# VDMEDA_DisplayMaster.net
KiCad netlist of a schematic drawn in Altium Designer
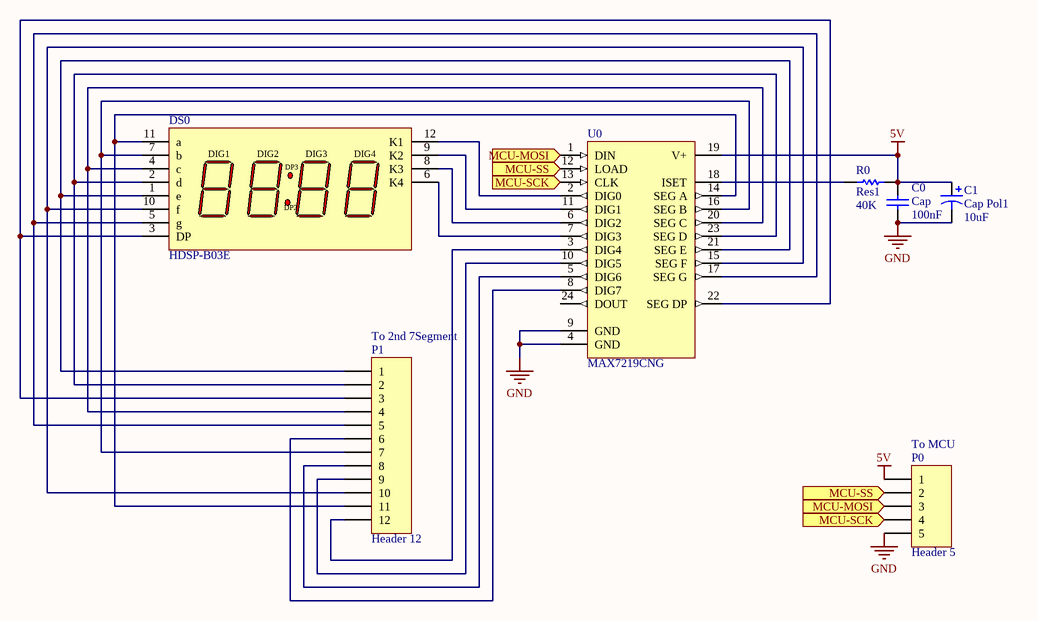
[diagram p0: VDMEDA_DisplayMaster.SchDoc]

(export (version "E")
  (design (tool "Eeschema 10.0.6"))
  (components
    (comp (ref "C0")
      (value "Cap")
      (footprint "RAD-0.3")
      (description "Capacitor")
      (fields (field (name "ALTIUM_VALUE") "100nF") (field (name "PUBLISHER") "Altium Limited"))
      (libsource (lib "Miscellaneous Devices") (part "Cap"))
    )
    (comp (ref "C1")
      (value "Cap Pol1")
      (footprint "RB7.6-15")
      (description "Polarized Capacitor (Radial)")
      (fields (field (name "ALTIUM_VALUE") "10uF") (field (name "PUBLISHER") "Altium Limited"))
      (libsource (lib "Miscellaneous Devices") (part "Cap Pol1"))
    )
    (comp (ref "DS0")
      (value "HDSP-B03E")
      (footprint "B-88")
      (description "14.22 mm GaP HER, Untinted, 88:88 4-Digit 7-Segment Display: CC, Gray Surface")
      (fields (field (name "PUBLISHER") "Altium Limited"))
      (libsource (lib "Agilent LED Display 7-Segment, 4-Digit") (part "HDSP-B03E"))
    )
    (comp (ref "P0")
      (value "Header 5")
      (footprint "HDR1X5")
      (description "Header, 5-Pin")
      (fields (field (name "PUBLISHER") "Altium Limited"))
      (libsource (lib "Miscellaneous Connectors") (part "Header 5"))
    )
    (comp (ref "P1")
      (value "Header 12")
      (footprint "HDR1X12")
      (description "Header, 12-Pin")
      (fields (field (name "PUBLISHER") "Altium Limited"))
      (libsource (lib "Miscellaneous Connectors") (part "Header 12"))
    )
    (comp (ref "R0")
      (value "Res1")
      (footprint "AXIAL-0.3")
      (description "Resistor")
      (fields (field (name "ALTIUM_VALUE") "40K") (field (name "PUBLISHER") "Altium Limited"))
      (libsource (lib "Miscellaneous Devices") (part "Res1"))
    )
    (comp (ref "U0")
      (value "MAX7219CNG")
      (footprint "NG24A")
      (description "Serially Interfaced, 8-Digit LED Display Driver")
      (fields (field (name "PUBLISHER") "Altium Limited"))
      (libsource (lib "Maxim Interface Display Driver") (part "MAX7219CNG"))
    )
  )
  (nets
    (net (code "1") (name "/MCU-MOSI") (class "Default")
      (node (ref "P0") (pin "3") (pinfunction "3_3") (pintype "passive"))
      (node (ref "U0") (pin "1") (pinfunction "DIN_1") (pintype "input"))
    )
    (net (code "2") (name "/MCU-SCK") (class "Default")
      (node (ref "P0") (pin "4") (pinfunction "4_4") (pintype "passive"))
      (node (ref "U0") (pin "13") (pinfunction "CLK_13") (pintype "input"))
    )
    (net (code "3") (name "/MCU-SS") (class "Default")
      (node (ref "P0") (pin "2") (pinfunction "2_2") (pintype "passive"))
      (node (ref "U0") (pin "12") (pinfunction "LOAD_12") (pintype "input"))
    )
    (net (code "4") (name "5V") (class "Default")
      (node (ref "C0") (pin "2") (pinfunction "2_2") (pintype "passive"))
      (node (ref "C1") (pin "1") (pinfunction "1_1") (pintype "passive"))
      (node (ref "P0") (pin "1") (pinfunction "1_1") (pintype "passive"))
      (node (ref "R0") (pin "2") (pinfunction "2_2") (pintype "passive"))
      (node (ref "U0") (pin "19") (pinfunction "V+_19") (pintype "power_in"))
    )
    (net (code "5") (name "GND") (class "Default")
      (node (ref "C0") (pin "1") (pinfunction "1_1") (pintype "passive"))
      (node (ref "C1") (pin "2") (pinfunction "2_2") (pintype "passive"))
      (node (ref "P0") (pin "5") (pinfunction "5_5") (pintype "passive"))
      (node (ref "U0") (pin "4") (pinfunction "GND_4") (pintype "power_in"))
      (node (ref "U0") (pin "9") (pinfunction "GND_9") (pintype "power_in"))
    )
    (net (code "6") (name "Net-(DS0-DP)") (class "Default")
      (node (ref "DS0") (pin "3") (pinfunction "DP_3") (pintype "passive"))
      (node (ref "P1") (pin "3") (pinfunction "3_3") (pintype "passive"))
      (node (ref "U0") (pin "22") (pinfunction "SEG_DP_22") (pintype "output"))
    )
    (net (code "7") (name "Net-(DS0-K1)") (class "Default")
      (node (ref "DS0") (pin "12") (pinfunction "K1_12") (pintype "passive"))
      (node (ref "U0") (pin "2") (pinfunction "DIG0_2") (pintype "output"))
    )
    (net (code "8") (name "Net-(DS0-K2)") (class "Default")
      (node (ref "DS0") (pin "9") (pinfunction "K2_9") (pintype "passive"))
      (node (ref "U0") (pin "11") (pinfunction "DIG1_11") (pintype "output"))
    )
    (net (code "9") (name "Net-(DS0-K3)") (class "Default")
      (node (ref "DS0") (pin "8") (pinfunction "K3_8") (pintype "passive"))
      (node (ref "U0") (pin "6") (pinfunction "DIG2_6") (pintype "output"))
    )
    (net (code "10") (name "Net-(DS0-K4)") (class "Default")
      (node (ref "DS0") (pin "6") (pinfunction "K4_6") (pintype "passive"))
      (node (ref "U0") (pin "7") (pinfunction "DIG3_7") (pintype "output"))
    )
    (net (code "11") (name "Net-(DS0-a)") (class "Default")
      (node (ref "DS0") (pin "11") (pinfunction "a_11") (pintype "passive"))
      (node (ref "P1") (pin "11") (pinfunction "11_11") (pintype "passive"))
      (node (ref "U0") (pin "14") (pinfunction "SEG_A_14") (pintype "output"))
    )
    (net (code "12") (name "Net-(DS0-b)") (class "Default")
      (node (ref "DS0") (pin "7") (pinfunction "b_7") (pintype "passive"))
      (node (ref "P1") (pin "7") (pinfunction "7_7") (pintype "passive"))
      (node (ref "U0") (pin "16") (pinfunction "SEG_B_16") (pintype "output"))
    )
    (net (code "13") (name "Net-(DS0-c)") (class "Default")
      (node (ref "DS0") (pin "4") (pinfunction "c_4") (pintype "passive"))
      (node (ref "P1") (pin "4") (pinfunction "4_4") (pintype "passive"))
      (node (ref "U0") (pin "20") (pinfunction "SEG_C_20") (pintype "output"))
    )
    (net (code "14") (name "Net-(DS0-d)") (class "Default")
      (node (ref "DS0") (pin "2") (pinfunction "d_2") (pintype "passive"))
      (node (ref "P1") (pin "2") (pinfunction "2_2") (pintype "passive"))
      (node (ref "U0") (pin "23") (pinfunction "SEG_D_23") (pintype "output"))
    )
    (net (code "15") (name "Net-(DS0-e)") (class "Default")
      (node (ref "DS0") (pin "1") (pinfunction "e_1") (pintype "passive"))
      (node (ref "P1") (pin "1") (pinfunction "1_1") (pintype "passive"))
      (node (ref "U0") (pin "21") (pinfunction "SEG_E_21") (pintype "output"))
    )
    (net (code "16") (name "Net-(DS0-f)") (class "Default")
      (node (ref "DS0") (pin "10") (pinfunction "f_10") (pintype "passive"))
      (node (ref "P1") (pin "10") (pinfunction "10_10") (pintype "passive"))
      (node (ref "U0") (pin "15") (pinfunction "SEG_F_15") (pintype "output"))
    )
    (net (code "17") (name "Net-(DS0-g)") (class "Default")
      (node (ref "DS0") (pin "5") (pinfunction "g_5") (pintype "passive"))
      (node (ref "P1") (pin "5") (pinfunction "5_5") (pintype "passive"))
      (node (ref "U0") (pin "17") (pinfunction "SEG_G_17") (pintype "output"))
    )
    (net (code "18") (name "Net-(U0-DIG4)") (class "Default")
      (node (ref "P1") (pin "12") (pinfunction "12_12") (pintype "passive"))
      (node (ref "U0") (pin "3") (pinfunction "DIG4_3") (pintype "output"))
    )
    (net (code "19") (name "Net-(U0-DIG5)") (class "Default")
      (node (ref "P1") (pin "9") (pinfunction "9_9") (pintype "passive"))
      (node (ref "U0") (pin "10") (pinfunction "DIG5_10") (pintype "output"))
    )
    (net (code "20") (name "Net-(U0-DIG6)") (class "Default")
      (node (ref "P1") (pin "8") (pinfunction "8_8") (pintype "passive"))
      (node (ref "U0") (pin "5") (pinfunction "DIG6_5") (pintype "output"))
    )
    (net (code "21") (name "Net-(U0-DIG7)") (class "Default")
      (node (ref "P1") (pin "6") (pinfunction "6_6") (pintype "passive"))
      (node (ref "U0") (pin "8") (pinfunction "DIG7_8") (pintype "output"))
    )
    (net (code "22") (name "Net-(U0-ISET)") (class "Default")
      (node (ref "R0") (pin "1") (pinfunction "1_1") (pintype "passive"))
      (node (ref "U0") (pin "18") (pinfunction "ISET_18") (pintype "passive"))
    )
    (net (code "23") (name "unconnected-(U0-DOUT-Pad24)") (class "Default")
      (node (ref "U0") (pin "24") (pinfunction "DOUT_24") (pintype "output"))
    )
  )
)
